# Micro4You.net
KiCad netlist of a schematic drawn in EAGLE
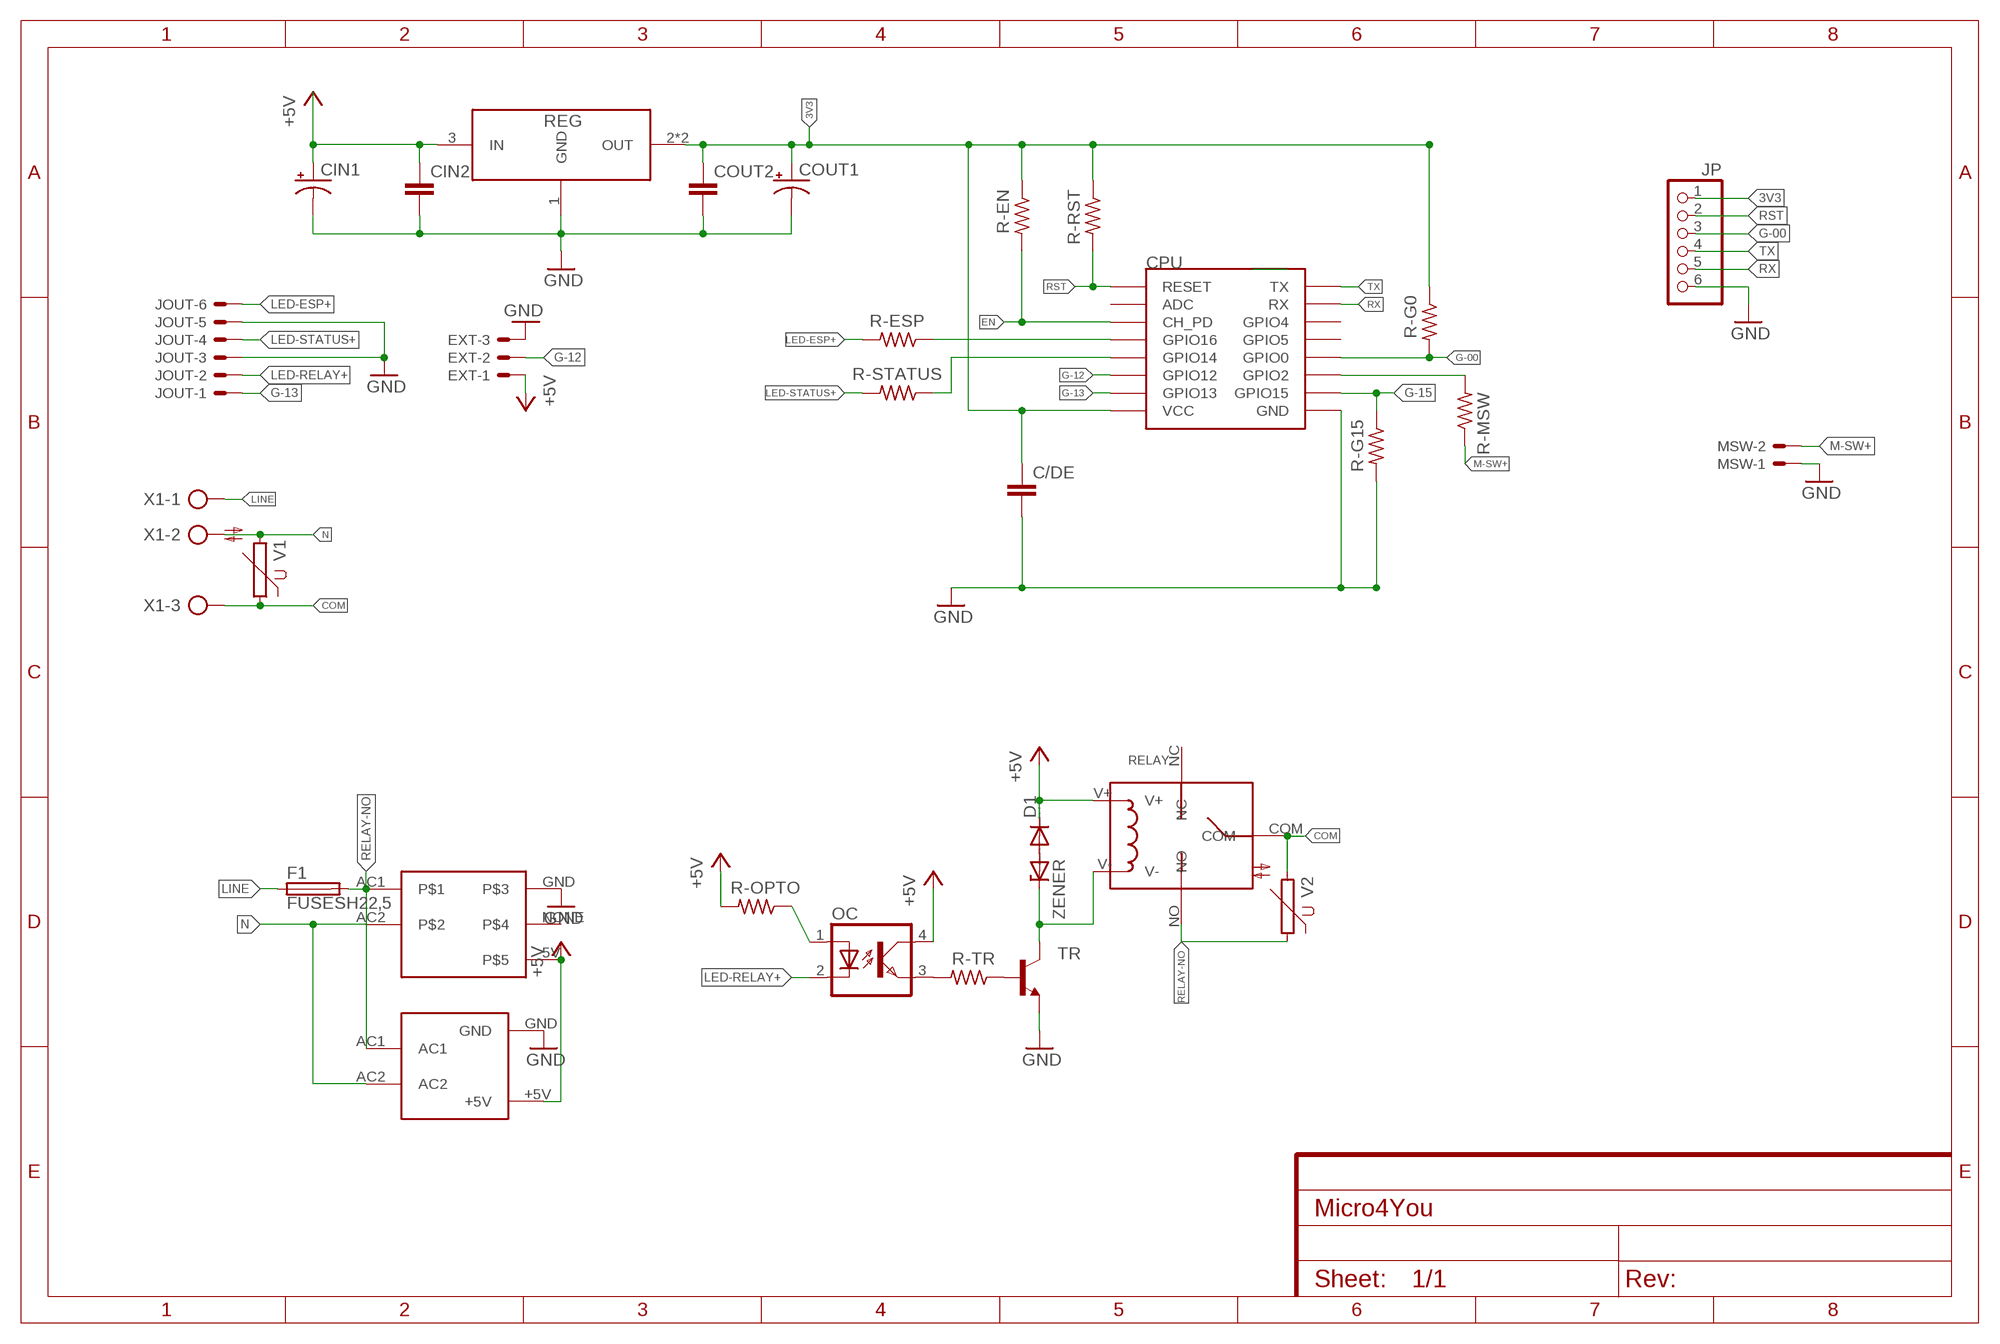
[diagram p0: schematic, sheet 1]

(export (version "E")
  (design (tool "Eeschema 10.0.6"))
  (components
    (comp (ref "C/DE")
      (value "C-EUC0805")
      (footprint "eagle-import:C0805")
      (libsource (lib "eagle-import") (part "C-EUC0805"))
    )
    (comp (ref "CIN1")
      (value "CPOL-USE2.5-5")
      (footprint "eagle-import:E2,5-5")
      (libsource (lib "eagle-import") (part "CPOL-USE2.5-5"))
    )
    (comp (ref "CIN2")
      (value "C-EUC0805")
      (footprint "eagle-import:C0805")
      (libsource (lib "eagle-import") (part "C-EUC0805"))
    )
    (comp (ref "COUT1")
      (value "CPOL-USE2.5-5")
      (footprint "eagle-import:E2,5-5")
      (libsource (lib "eagle-import") (part "CPOL-USE2.5-5"))
    )
    (comp (ref "COUT2")
      (value "C-EUC0805")
      (footprint "eagle-import:C0805")
      (libsource (lib "eagle-import") (part "C-EUC0805"))
    )
    (comp (ref "CPU")
      (value "ESP12SMD")
      (footprint "eagle-import:ESP12-SMD")
      (libsource (lib "eagle-import") (part "ESP12SMD"))
    )
    (comp (ref "D1")
      (value "1N4148DO35-7")
      (footprint "eagle-import:DO35-7")
      (libsource (lib "eagle-import") (part "1N4148DO35-7"))
    )
    (comp (ref "EXT")
      (value "53048-03")
      (footprint "eagle-import:53048-03")
      (fields (field (name "MF") "WALDOM/MOLEX") (field (name "MPN") "53048-0310"))
      (libsource (lib "eagle-import") (part "53?-03048"))
    )
    (comp (ref "F1")
      (value "FUSESH22,5")
      (footprint "eagle-import:SH22,5")
      (libsource (lib "eagle-import") (part "FUSESH22,5"))
    )
    (comp (ref "HLK")
      (value "HLK-PM01")
      (footprint "eagle-import:HLK-PM01")
      (libsource (lib "eagle-import") (part "HLK-PM01"))
    )
    (comp (ref "JOUT")
      (value "53048-06")
      (footprint "eagle-import:53048-06")
      (fields (field (name "MF") "WALDOM/MOLEX") (field (name "MPN") "53048-0610"))
      (libsource (lib "eagle-import") (part "53?-06048"))
    )
    (comp (ref "JP")
      (value "PINHD-1X6")
      (footprint "eagle-import:1X06")
      (libsource (lib "eagle-import") (part "PINHD-1X6"))
    )
    (comp (ref "MSW")
      (value "53048-02")
      (footprint "eagle-import:53048-02")
      (fields (field (name "MF") "MOLEX") (field (name "MPN") "53048-0210"))
      (libsource (lib "eagle-import") (part "53?-02048"))
    )
    (comp (ref "OC")
      (value "PC817")
      (footprint "eagle-import:DIL04")
      (fields (field (name "MPN") "PC817X4J000F"))
      (libsource (lib "eagle-import") (part "PC817"))
    )
    (comp (ref "R-EN")
      (value "R-US_M0805")
      (footprint "eagle-import:M0805")
      (libsource (lib "eagle-import") (part "R-US_M0805"))
    )
    (comp (ref "R-ESP")
      (value "R-US_M0805")
      (footprint "eagle-import:M0805")
      (libsource (lib "eagle-import") (part "R-US_M0805"))
    )
    (comp (ref "R-G0")
      (value "R-US_M0805")
      (footprint "eagle-import:M0805")
      (libsource (lib "eagle-import") (part "R-US_M0805"))
    )
    (comp (ref "R-G15")
      (value "R-US_M0805")
      (footprint "eagle-import:M0805")
      (libsource (lib "eagle-import") (part "R-US_M0805"))
    )
    (comp (ref "R-MSW")
      (value "R-US_M0805")
      (footprint "eagle-import:M0805")
      (libsource (lib "eagle-import") (part "R-US_M0805"))
    )
    (comp (ref "R-OPTO")
      (value "R-US_M0805")
      (footprint "eagle-import:M0805")
      (libsource (lib "eagle-import") (part "R-US_M0805"))
    )
    (comp (ref "R-RST")
      (value "R-US_M0805")
      (footprint "eagle-import:M0805")
      (libsource (lib "eagle-import") (part "R-US_M0805"))
    )
    (comp (ref "R-STATUS")
      (value "R-US_M0805")
      (footprint "eagle-import:M0805")
      (libsource (lib "eagle-import") (part "R-US_M0805"))
    )
    (comp (ref "R-TR")
      (value "R-US_M0805")
      (footprint "eagle-import:M0805")
      (libsource (lib "eagle-import") (part "R-US_M0805"))
    )
    (comp (ref "REG")
      (value "AMS1117-3.3")
      (footprint "eagle-import:SOT-223")
      (libsource (lib "eagle-import") (part "AMS1117-3.3"))
    )
    (comp (ref "RELAY")
      (value "RELAY-SONGLE")
      (footprint "eagle-import:RELAY-SONGLE")
      (libsource (lib "eagle-import") (part "RELAY-SONGLE"))
    )
    (comp (ref "TR")
      (value "BC817-16SMD")
      (footprint "eagle-import:SOT23-BEC")
      (libsource (lib "eagle-import") (part "BC817SMD-16"))
    )
    (comp (ref "U$4")
      (value "POWERSUPPLY-5V-700MA")
      (footprint "eagle-import:POWERSUPPLY-5V-700MA")
      (libsource (lib "eagle-import") (part "POWERSUPPLY-5V-700MA"))
    )
    (comp (ref "V1")
      (value "S14K11")
      (footprint "eagle-import:S14K11")
      (libsource (lib "eagle-import") (part "S14K11"))
    )
    (comp (ref "V2")
      (value "S14K11")
      (footprint "eagle-import:S14K11")
      (libsource (lib "eagle-import") (part "S14K11"))
    )
    (comp (ref "X1")
      (value "AK300/3")
      (footprint "eagle-import:AK300_3")
      (libsource (lib "eagle-import") (part "AK300/3"))
    )
    (comp (ref "ZENER")
      (value "1N4728")
      (footprint "eagle-import:DO41Z10")
      (libsource (lib "eagle-import") (part "1N4728"))
    )
  )
  (nets
    (net (code "1") (name "+5V") (class "Default")
      (node (ref "CIN1") (pin "+") (pinfunction "+_+") (pintype "passive"))
      (node (ref "CIN2") (pin "1") (pinfunction "1_1") (pintype "passive"))
      (node (ref "D1") (pin "C") (pinfunction "C_C") (pintype "passive"))
      (node (ref "EXT") (pin "1") (pinfunction "S_1") (pintype "passive"))
      (node (ref "HLK") (pin "+5V") (pinfunction "+5V_+5V") (pintype "bidirectional"))
      (node (ref "OC") (pin "4") (pinfunction "COL_4") (pintype "passive"))
      (node (ref "R-OPTO") (pin "2") (pinfunction "2_2") (pintype "passive"))
      (node (ref "REG") (pin "3") (pinfunction "IN_3") (pintype "input"))
      (node (ref "RELAY") (pin "V+") (pinfunction "V+_V+") (pintype "bidirectional"))
      (node (ref "U$4") (pin "5V") (pinfunction "P$5_5V") (pintype "bidirectional"))
    )
    (net (code "2") (name "3V3") (class "Default")
      (node (ref "C/DE") (pin "1") (pinfunction "1_1") (pintype "passive"))
      (node (ref "COUT1") (pin "+") (pinfunction "+_+") (pintype "passive"))
      (node (ref "COUT2") (pin "1") (pinfunction "1_1") (pintype "passive"))
      (node (ref "CPU") (pin "VCC") (pinfunction "VCC_VCC") (pintype "bidirectional"))
      (node (ref "JP") (pin "1") (pinfunction "1_1") (pintype "passive"))
      (node (ref "R-EN") (pin "1") (pinfunction "1_1") (pintype "passive"))
      (node (ref "R-G0") (pin "1") (pinfunction "1_1") (pintype "passive"))
      (node (ref "R-RST") (pin "1") (pinfunction "1_1") (pintype "passive"))
      (node (ref "REG") (pin "2") (pinfunction "OUT_2") (pintype "output"))
      (node (ref "REG") (pin "4") (pinfunction "OUT_4") (pintype "output"))
    )
    (net (code "3") (name "COM") (class "Default")
      (node (ref "RELAY") (pin "COM") (pinfunction "COM_COM") (pintype "bidirectional"))
      (node (ref "V1") (pin "1") (pinfunction "1_1") (pintype "passive"))
      (node (ref "V2") (pin "2") (pinfunction "2_2") (pintype "passive"))
      (node (ref "X1") (pin "3") (pinfunction "KL_3") (pintype "passive"))
    )
    (net (code "4") (name "EN") (class "Default")
      (node (ref "CPU") (pin "CH_PD") (pinfunction "CH_PD_CH_PD") (pintype "bidirectional"))
      (node (ref "R-EN") (pin "2") (pinfunction "2_2") (pintype "passive"))
    )
    (net (code "5") (name "G-00") (class "Default")
      (node (ref "CPU") (pin "GPIO0") (pinfunction "GPIO0_GPIO0") (pintype "bidirectional"))
      (node (ref "JP") (pin "3") (pinfunction "3_3") (pintype "passive"))
      (node (ref "R-G0") (pin "2") (pinfunction "2_2") (pintype "passive"))
    )
    (net (code "6") (name "G-12") (class "Default")
      (node (ref "CPU") (pin "GPIO12") (pinfunction "GPIO12_GPIO12") (pintype "bidirectional"))
      (node (ref "EXT") (pin "2") (pinfunction "S_2") (pintype "passive"))
    )
    (net (code "7") (name "G-13") (class "Default")
      (node (ref "CPU") (pin "GPIO13") (pinfunction "GPIO13_GPIO13") (pintype "bidirectional"))
      (node (ref "JOUT") (pin "1") (pinfunction "S_1") (pintype "passive"))
    )
    (net (code "8") (name "G-15") (class "Default")
      (node (ref "CPU") (pin "GPIO15") (pinfunction "GPIO15_GPIO15") (pintype "bidirectional"))
      (node (ref "R-G15") (pin "1") (pinfunction "1_1") (pintype "passive"))
    )
    (net (code "9") (name "GND") (class "Default")
      (node (ref "C/DE") (pin "2") (pinfunction "2_2") (pintype "passive"))
      (node (ref "CIN1") (pin "-") (pinfunction "-_-") (pintype "passive"))
      (node (ref "CIN2") (pin "2") (pinfunction "2_2") (pintype "passive"))
      (node (ref "COUT1") (pin "-") (pinfunction "-_-") (pintype "passive"))
      (node (ref "COUT2") (pin "2") (pinfunction "2_2") (pintype "passive"))
      (node (ref "CPU") (pin "GND") (pinfunction "GND_GND") (pintype "bidirectional"))
      (node (ref "EXT") (pin "3") (pinfunction "S_3") (pintype "passive"))
      (node (ref "HLK") (pin "GND") (pinfunction "GND_GND") (pintype "bidirectional"))
      (node (ref "JOUT") (pin "3") (pinfunction "S_3") (pintype "passive"))
      (node (ref "JOUT") (pin "5") (pinfunction "S_5") (pintype "passive"))
      (node (ref "JP") (pin "6") (pinfunction "6_6") (pintype "passive"))
      (node (ref "MSW") (pin "1") (pinfunction "S_1") (pintype "passive"))
      (node (ref "R-G15") (pin "2") (pinfunction "2_2") (pintype "passive"))
      (node (ref "REG") (pin "1") (pinfunction "GND_1") (pintype "passive"))
      (node (ref "TR") (pin "E") (pinfunction "E_E") (pintype "passive"))
      (node (ref "U$4") (pin "GND") (pinfunction "P$3_GND") (pintype "bidirectional"))
    )
    (net (code "10") (name "LED-ESP+") (class "Default")
      (node (ref "JOUT") (pin "6") (pinfunction "S_6") (pintype "passive"))
      (node (ref "R-ESP") (pin "2") (pinfunction "2_2") (pintype "passive"))
    )
    (net (code "11") (name "LED-RELAY+") (class "Default")
      (node (ref "JOUT") (pin "2") (pinfunction "S_2") (pintype "passive"))
      (node (ref "OC") (pin "2") (pinfunction "C_2") (pintype "passive"))
    )
    (net (code "12") (name "LED-STATUS+") (class "Default")
      (node (ref "JOUT") (pin "4") (pinfunction "S_4") (pintype "passive"))
      (node (ref "R-STATUS") (pin "2") (pinfunction "2_2") (pintype "passive"))
    )
    (net (code "13") (name "LINE") (class "Default")
      (node (ref "F1") (pin "1") (pinfunction "1_1") (pintype "passive"))
      (node (ref "X1") (pin "1") (pinfunction "KL_1") (pintype "passive"))
    )
    (net (code "14") (name "M-SW+") (class "Default")
      (node (ref "MSW") (pin "2") (pinfunction "S_2") (pintype "passive"))
      (node (ref "R-MSW") (pin "1") (pinfunction "1_1") (pintype "passive"))
    )
    (net (code "15") (name "N") (class "Default")
      (node (ref "HLK") (pin "AC2") (pinfunction "AC2_AC2") (pintype "bidirectional"))
      (node (ref "U$4") (pin "AC2") (pinfunction "P$2_AC2") (pintype "bidirectional"))
      (node (ref "V1") (pin "2") (pinfunction "2_2") (pintype "passive"))
      (node (ref "X1") (pin "2") (pinfunction "KL_2") (pintype "passive"))
    )
    (net (code "16") (name "Net-(CPU-PadGPIO2)") (class "Default")
      (node (ref "CPU") (pin "GPIO2") (pinfunction "GPIO2_GPIO2") (pintype "bidirectional"))
      (node (ref "R-MSW") (pin "2") (pinfunction "2_2") (pintype "passive"))
    )
    (net (code "17") (name "Net-(CPU-PadGPIO14)") (class "Default")
      (node (ref "CPU") (pin "GPIO14") (pinfunction "GPIO14_GPIO14") (pintype "bidirectional"))
      (node (ref "R-STATUS") (pin "1") (pinfunction "1_1") (pintype "passive"))
    )
    (net (code "18") (name "Net-(CPU-PadGPIO16)") (class "Default")
      (node (ref "CPU") (pin "GPIO16") (pinfunction "GPIO16_GPIO16") (pintype "bidirectional"))
      (node (ref "R-ESP") (pin "1") (pinfunction "1_1") (pintype "passive"))
    )
    (net (code "19") (name "Net-(D1-PadA)") (class "Default")
      (node (ref "D1") (pin "A") (pinfunction "A_A") (pintype "passive"))
      (node (ref "ZENER") (pin "A") (pinfunction "A_A") (pintype "passive"))
    )
    (net (code "20") (name "Net-(OC-A)") (class "Default")
      (node (ref "OC") (pin "1") (pinfunction "A_1") (pintype "passive"))
      (node (ref "R-OPTO") (pin "1") (pinfunction "1_1") (pintype "passive"))
    )
    (net (code "21") (name "Net-(OC-EMIT)") (class "Default")
      (node (ref "OC") (pin "3") (pinfunction "EMIT_3") (pintype "passive"))
      (node (ref "R-TR") (pin "2") (pinfunction "2_2") (pintype "passive"))
    )
    (net (code "22") (name "Net-(R-TR-Pad1)") (class "Default")
      (node (ref "R-TR") (pin "1") (pinfunction "1_1") (pintype "passive"))
      (node (ref "TR") (pin "B") (pinfunction "B_B") (pintype "passive"))
    )
    (net (code "23") (name "Net-(RELAY-PadV-)") (class "Default")
      (node (ref "RELAY") (pin "V-") (pinfunction "V-_V-") (pintype "bidirectional"))
      (node (ref "TR") (pin "C") (pinfunction "C_C") (pintype "passive"))
      (node (ref "ZENER") (pin "C") (pinfunction "C_C") (pintype "passive"))
    )
    (net (code "24") (name "RELAY-NO") (class "Default")
      (node (ref "F1") (pin "2") (pinfunction "2_2") (pintype "passive"))
      (node (ref "HLK") (pin "AC1") (pinfunction "AC1_AC1") (pintype "bidirectional"))
      (node (ref "RELAY") (pin "NO") (pinfunction "NO_NO") (pintype "bidirectional"))
      (node (ref "U$4") (pin "AC1") (pinfunction "P$1_AC1") (pintype "bidirectional"))
      (node (ref "V2") (pin "1") (pinfunction "1_1") (pintype "passive"))
    )
    (net (code "25") (name "RST") (class "Default")
      (node (ref "CPU") (pin "RESET") (pinfunction "RESET_RESET") (pintype "bidirectional"))
      (node (ref "JP") (pin "2") (pinfunction "2_2") (pintype "passive"))
      (node (ref "R-RST") (pin "2") (pinfunction "2_2") (pintype "passive"))
    )
    (net (code "26") (name "RX") (class "Default")
      (node (ref "CPU") (pin "RXD0") (pinfunction "RX_RXD0") (pintype "bidirectional"))
      (node (ref "JP") (pin "5") (pinfunction "5_5") (pintype "passive"))
    )
    (net (code "27") (name "TX") (class "Default")
      (node (ref "CPU") (pin "TXD0") (pinfunction "TX_TXD0") (pintype "bidirectional"))
      (node (ref "JP") (pin "4") (pinfunction "4_4") (pintype "passive"))
    )
    (net (code "28") (name "unconnected-(CPU-PadADC)") (class "Default")
      (node (ref "CPU") (pin "ADC") (pinfunction "ADC_ADC") (pintype "bidirectional"))
    )
    (net (code "29") (name "unconnected-(CPU-PadGPIO4)") (class "Default")
      (node (ref "CPU") (pin "GPIO4") (pinfunction "GPIO4_GPIO4") (pintype "bidirectional"))
    )
    (net (code "30") (name "unconnected-(CPU-PadGPIO5)") (class "Default")
      (node (ref "CPU") (pin "GPIO5") (pinfunction "GPIO5_GPIO5") (pintype "bidirectional"))
    )
    (net (code "31") (name "unconnected-(RELAY-PadNC)") (class "Default")
      (node (ref "RELAY") (pin "NC") (pinfunction "NC_NC") (pintype "bidirectional"))
    )
    (net (code "32") (name "unconnected-(U$4-P$4-PadNONE)") (class "Default")
      (node (ref "U$4") (pin "NONE") (pinfunction "P$4_NONE") (pintype "bidirectional"))
    )
  )
)
